# BatteryBoard.net
KiCad netlist of a schematic drawn in EAGLE
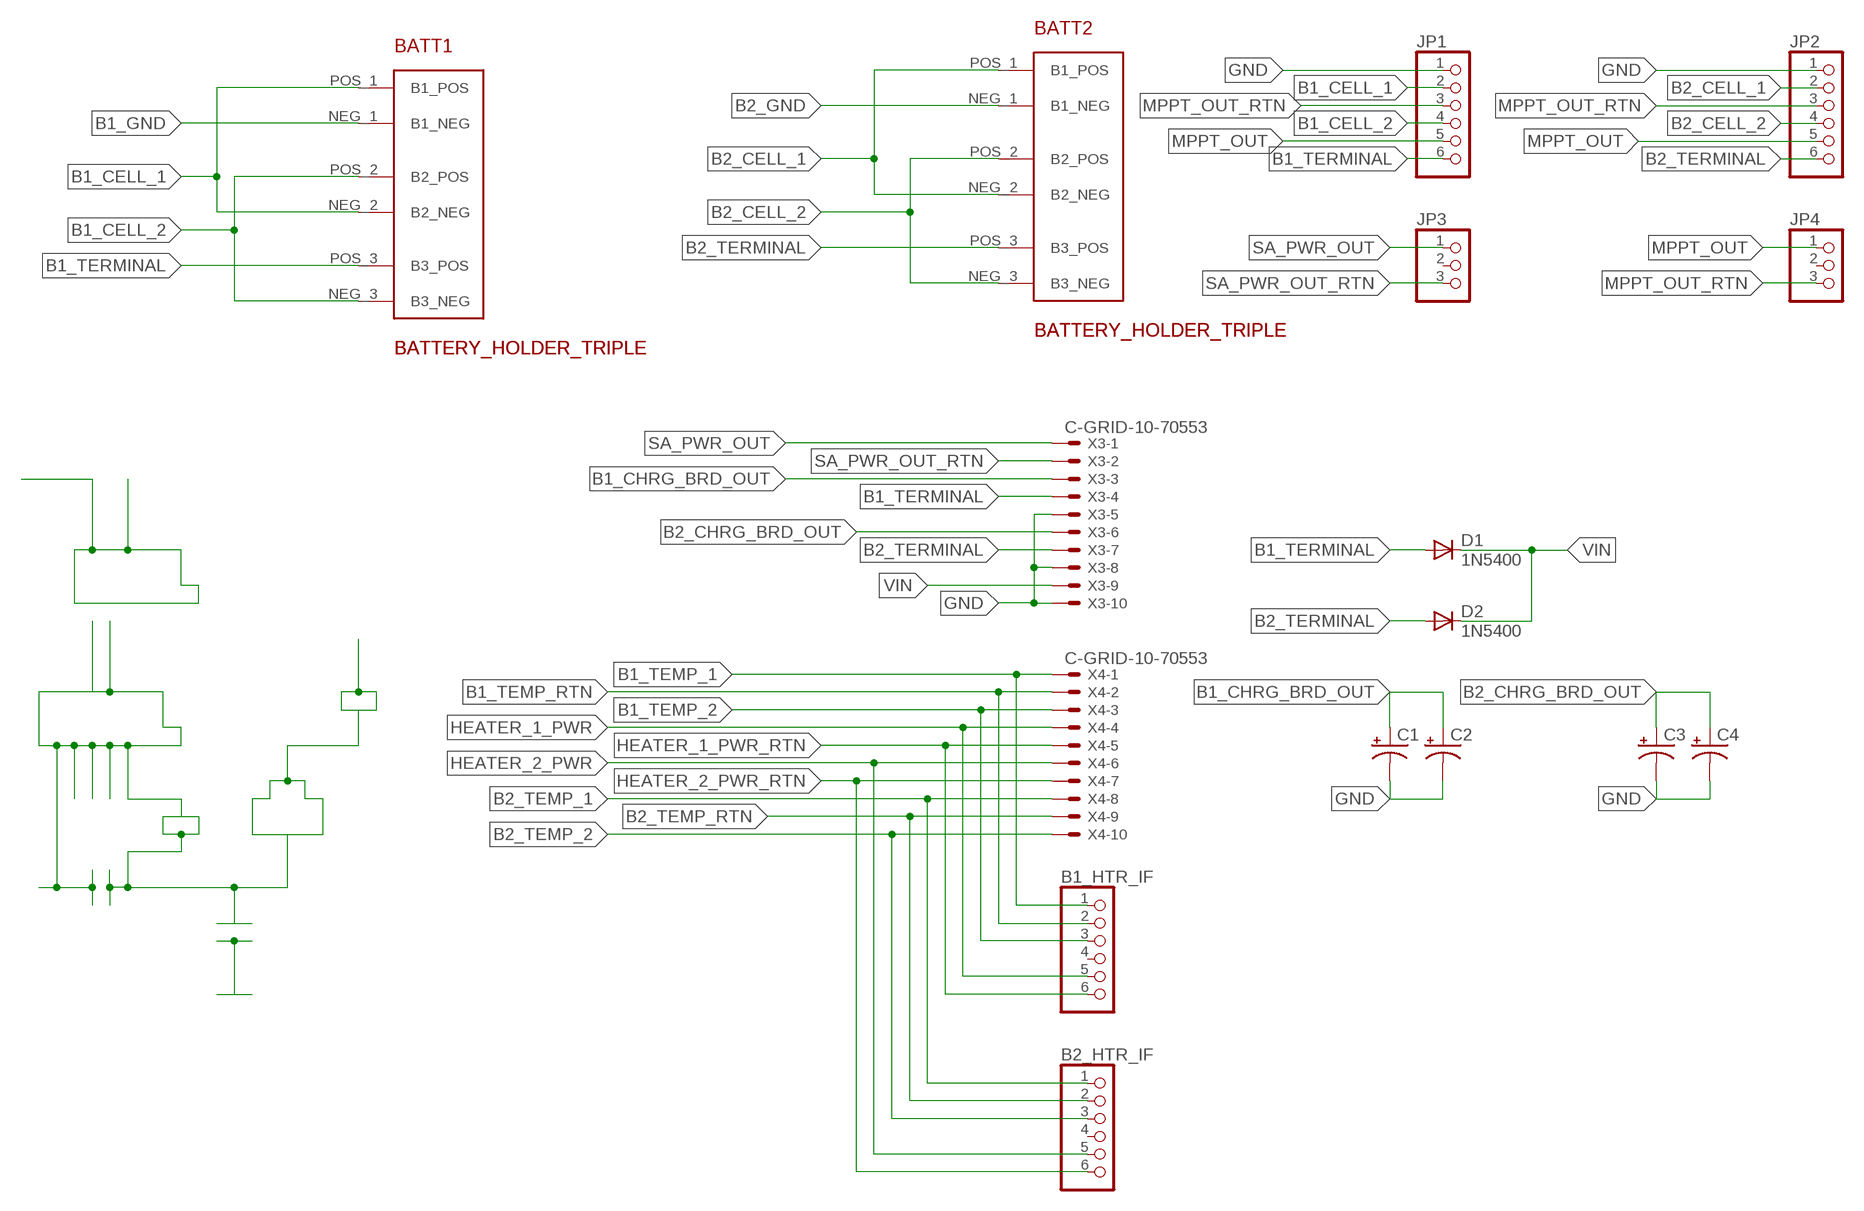
[diagram p0: schematic, sheet 1]

(export (version "E")
  (design (tool "Eeschema 10.0.6"))
  (components
    (comp (ref "B1_HTR_IF")
      (value "PINHD-1X6CLEAN")
      (footprint "eagle-import:1X06-CLEAN")
      (libsource (lib "eagle-import") (part "PINHD-1X6CLEAN"))
    )
    (comp (ref "B2_HTR_IF")
      (value "PINHD-1X6CLEAN")
      (footprint "eagle-import:1X06-CLEAN")
      (libsource (lib "eagle-import") (part "PINHD-1X6CLEAN"))
    )
    (comp (ref "BATT1")
      (value "BATTERY_HOLDER_TRIPLE")
      (footprint "eagle-import:BATT_HOLDER_SINGLE")
      (libsource (lib "eagle-import") (part "BATTERY_HOLDER_TRIPLE"))
    )
    (comp (ref "BATT2")
      (value "BATTERY_HOLDER_TRIPLE")
      (footprint "eagle-import:BATT_HOLDER_SINGLE")
      (libsource (lib "eagle-import") (part "BATTERY_HOLDER_TRIPLE"))
    )
    (comp (ref "C1")
      (value "CPOL-USCT7343")
      (footprint "eagle-import:CT7343")
      (libsource (lib "eagle-import") (part "CPOL-USCT7343"))
    )
    (comp (ref "C2")
      (value "CPOL-USCT7343")
      (footprint "eagle-import:CT7343")
      (libsource (lib "eagle-import") (part "CPOL-USCT7343"))
    )
    (comp (ref "C3")
      (value "CPOL-USCT7343")
      (footprint "eagle-import:CT7343")
      (libsource (lib "eagle-import") (part "CPOL-USCT7343"))
    )
    (comp (ref "C4")
      (value "CPOL-USCT7343")
      (footprint "eagle-import:CT7343")
      (libsource (lib "eagle-import") (part "CPOL-USCT7343"))
    )
    (comp (ref "D1")
      (value "1N5400")
      (footprint "eagle-import:DO201-15")
      (libsource (lib "eagle-import") (part "1N5400"))
    )
    (comp (ref "D2")
      (value "1N5400")
      (footprint "eagle-import:DO201-15")
      (libsource (lib "eagle-import") (part "1N5400"))
    )
    (comp (ref "JP1")
      (value "PINHD-1X6CLEAN")
      (footprint "eagle-import:1X06-CLEAN")
      (libsource (lib "eagle-import") (part "PINHD-1X6CLEAN"))
    )
    (comp (ref "JP2")
      (value "PINHD-1X6CLEAN")
      (footprint "eagle-import:1X06-CLEAN")
      (libsource (lib "eagle-import") (part "PINHD-1X6CLEAN"))
    )
    (comp (ref "JP3")
      (value "PINHD-1X3")
      (footprint "eagle-import:1X03")
      (libsource (lib "eagle-import") (part "PINHD-1X3"))
    )
    (comp (ref "JP4")
      (value "PINHD-1X3")
      (footprint "eagle-import:1X03")
      (libsource (lib "eagle-import") (part "PINHD-1X3"))
    )
    (comp (ref "X3")
      (value "C-GRID-10-70553")
      (footprint "eagle-import:70553-10")
      (libsource (lib "eagle-import") (part "C-GRID-10-70553"))
    )
    (comp (ref "X4")
      (value "C-GRID-10-70553")
      (footprint "eagle-import:70553-10")
      (libsource (lib "eagle-import") (part "C-GRID-10-70553"))
    )
  )
  (nets
    (net (code "1") (name "B1_CELL_1") (class "Default")
      (node (ref "BATT1") (pin "NEG_2") (pinfunction "B2_NEG_NEG_2") (pintype "bidirectional"))
      (node (ref "BATT1") (pin "POS_1") (pinfunction "B1_POS_POS_1") (pintype "bidirectional"))
      (node (ref "JP1") (pin "2") (pinfunction "2_2") (pintype "passive"))
    )
    (net (code "2") (name "B1_CELL_2") (class "Default")
      (node (ref "BATT1") (pin "NEG_3") (pinfunction "B3_NEG_NEG_3") (pintype "bidirectional"))
      (node (ref "BATT1") (pin "POS_2") (pinfunction "B2_POS_POS_2") (pintype "bidirectional"))
      (node (ref "JP1") (pin "4") (pinfunction "4_4") (pintype "passive"))
    )
    (net (code "3") (name "B1_CHRG_BRD_OUT") (class "Default")
      (node (ref "C1") (pin "+") (pinfunction "+_+") (pintype "passive"))
      (node (ref "C2") (pin "+") (pinfunction "+_+") (pintype "passive"))
      (node (ref "X3") (pin "3") (pinfunction "S_3") (pintype "passive"))
    )
    (net (code "4") (name "B1_GND") (class "Default")
      (node (ref "BATT1") (pin "NEG_1") (pinfunction "B1_NEG_NEG_1") (pintype "bidirectional"))
    )
    (net (code "5") (name "B1_TEMP_1") (class "Default")
      (node (ref "B1_HTR_IF") (pin "1") (pinfunction "1_1") (pintype "passive"))
      (node (ref "X4") (pin "1") (pinfunction "S_1") (pintype "passive"))
    )
    (net (code "6") (name "B1_TEMP_2") (class "Default")
      (node (ref "B1_HTR_IF") (pin "3") (pinfunction "3_3") (pintype "passive"))
      (node (ref "X4") (pin "3") (pinfunction "S_3") (pintype "passive"))
    )
    (net (code "7") (name "B1_TEMP_RTN") (class "Default")
      (node (ref "B1_HTR_IF") (pin "2") (pinfunction "2_2") (pintype "passive"))
      (node (ref "X4") (pin "2") (pinfunction "S_2") (pintype "passive"))
    )
    (net (code "8") (name "B1_TERMINAL") (class "Default")
      (node (ref "BATT1") (pin "POS_3") (pinfunction "B3_POS_POS_3") (pintype "bidirectional"))
      (node (ref "D1") (pin "A") (pinfunction "A_A") (pintype "passive"))
      (node (ref "JP1") (pin "6") (pinfunction "6_6") (pintype "passive"))
      (node (ref "X3") (pin "4") (pinfunction "S_4") (pintype "passive"))
    )
    (net (code "9") (name "B2_CELL_1") (class "Default")
      (node (ref "BATT2") (pin "NEG_2") (pinfunction "B2_NEG_NEG_2") (pintype "bidirectional"))
      (node (ref "BATT2") (pin "POS_1") (pinfunction "B1_POS_POS_1") (pintype "bidirectional"))
      (node (ref "JP2") (pin "2") (pinfunction "2_2") (pintype "passive"))
    )
    (net (code "10") (name "B2_CELL_2") (class "Default")
      (node (ref "BATT2") (pin "NEG_3") (pinfunction "B3_NEG_NEG_3") (pintype "bidirectional"))
      (node (ref "BATT2") (pin "POS_2") (pinfunction "B2_POS_POS_2") (pintype "bidirectional"))
      (node (ref "JP2") (pin "4") (pinfunction "4_4") (pintype "passive"))
    )
    (net (code "11") (name "B2_CHRG_BRD_OUT") (class "Default")
      (node (ref "C3") (pin "+") (pinfunction "+_+") (pintype "passive"))
      (node (ref "C4") (pin "+") (pinfunction "+_+") (pintype "passive"))
      (node (ref "X3") (pin "6") (pinfunction "S_6") (pintype "passive"))
    )
    (net (code "12") (name "B2_GND") (class "Default")
      (node (ref "BATT2") (pin "NEG_1") (pinfunction "B1_NEG_NEG_1") (pintype "bidirectional"))
    )
    (net (code "13") (name "B2_TEMP_1") (class "Default")
      (node (ref "B2_HTR_IF") (pin "1") (pinfunction "1_1") (pintype "passive"))
      (node (ref "X4") (pin "8") (pinfunction "S_8") (pintype "passive"))
    )
    (net (code "14") (name "B2_TEMP_2") (class "Default")
      (node (ref "B2_HTR_IF") (pin "3") (pinfunction "3_3") (pintype "passive"))
      (node (ref "X4") (pin "10") (pinfunction "S_10") (pintype "passive"))
    )
    (net (code "15") (name "B2_TEMP_RTN") (class "Default")
      (node (ref "B2_HTR_IF") (pin "2") (pinfunction "2_2") (pintype "passive"))
      (node (ref "X4") (pin "9") (pinfunction "S_9") (pintype "passive"))
    )
    (net (code "16") (name "B2_TERMINAL") (class "Default")
      (node (ref "BATT2") (pin "POS_3") (pinfunction "B3_POS_POS_3") (pintype "bidirectional"))
      (node (ref "D2") (pin "A") (pinfunction "A_A") (pintype "passive"))
      (node (ref "JP2") (pin "6") (pinfunction "6_6") (pintype "passive"))
      (node (ref "X3") (pin "7") (pinfunction "S_7") (pintype "passive"))
    )
    (net (code "17") (name "GND") (class "Default")
      (node (ref "C1") (pin "-") (pinfunction "-_-") (pintype "passive"))
      (node (ref "C2") (pin "-") (pinfunction "-_-") (pintype "passive"))
      (node (ref "C3") (pin "-") (pinfunction "-_-") (pintype "passive"))
      (node (ref "C4") (pin "-") (pinfunction "-_-") (pintype "passive"))
      (node (ref "JP1") (pin "1") (pinfunction "1_1") (pintype "passive"))
      (node (ref "JP2") (pin "1") (pinfunction "1_1") (pintype "passive"))
      (node (ref "X3") (pin "10") (pinfunction "S_10") (pintype "passive"))
      (node (ref "X3") (pin "5") (pinfunction "S_5") (pintype "passive"))
      (node (ref "X3") (pin "8") (pinfunction "S_8") (pintype "passive"))
    )
    (net (code "18") (name "HEATER_1_PWR") (class "Default")
      (node (ref "B1_HTR_IF") (pin "5") (pinfunction "5_5") (pintype "passive"))
      (node (ref "X4") (pin "4") (pinfunction "S_4") (pintype "passive"))
    )
    (net (code "19") (name "HEATER_1_PWR_RTN") (class "Default")
      (node (ref "B1_HTR_IF") (pin "6") (pinfunction "6_6") (pintype "passive"))
      (node (ref "X4") (pin "5") (pinfunction "S_5") (pintype "passive"))
    )
    (net (code "20") (name "HEATER_2_PWR") (class "Default")
      (node (ref "B2_HTR_IF") (pin "5") (pinfunction "5_5") (pintype "passive"))
      (node (ref "X4") (pin "6") (pinfunction "S_6") (pintype "passive"))
    )
    (net (code "21") (name "HEATER_2_PWR_RTN") (class "Default")
      (node (ref "B2_HTR_IF") (pin "6") (pinfunction "6_6") (pintype "passive"))
      (node (ref "X4") (pin "7") (pinfunction "S_7") (pintype "passive"))
    )
    (net (code "22") (name "MPPT_OUT") (class "Default")
      (node (ref "JP1") (pin "5") (pinfunction "5_5") (pintype "passive"))
      (node (ref "JP2") (pin "5") (pinfunction "5_5") (pintype "passive"))
      (node (ref "JP4") (pin "1") (pinfunction "1_1") (pintype "passive"))
    )
    (net (code "23") (name "MPPT_OUT_RTN") (class "Default")
      (node (ref "JP1") (pin "3") (pinfunction "3_3") (pintype "passive"))
      (node (ref "JP2") (pin "3") (pinfunction "3_3") (pintype "passive"))
      (node (ref "JP4") (pin "3") (pinfunction "3_3") (pintype "passive"))
    )
    (net (code "24") (name "SA_PWR_OUT") (class "Default")
      (node (ref "JP3") (pin "1") (pinfunction "1_1") (pintype "passive"))
      (node (ref "X3") (pin "1") (pinfunction "S_1") (pintype "passive"))
    )
    (net (code "25") (name "SA_PWR_OUT_RTN") (class "Default")
      (node (ref "JP3") (pin "3") (pinfunction "3_3") (pintype "passive"))
      (node (ref "X3") (pin "2") (pinfunction "S_2") (pintype "passive"))
    )
    (net (code "26") (name "VIN") (class "Default")
      (node (ref "D1") (pin "C") (pinfunction "C_C") (pintype "passive"))
      (node (ref "D2") (pin "C") (pinfunction "C_C") (pintype "passive"))
      (node (ref "X3") (pin "9") (pinfunction "S_9") (pintype "passive"))
    )
    (net (code "27") (name "unconnected-(B1_HTR_IF-Pad4)") (class "Default")
      (node (ref "B1_HTR_IF") (pin "4") (pinfunction "4_4") (pintype "passive"))
    )
    (net (code "28") (name "unconnected-(B2_HTR_IF-Pad4)") (class "Default")
      (node (ref "B2_HTR_IF") (pin "4") (pinfunction "4_4") (pintype "passive"))
    )
    (net (code "29") (name "unconnected-(JP3-Pad2)") (class "Default")
      (node (ref "JP3") (pin "2") (pinfunction "2_2") (pintype "passive"))
    )
    (net (code "30") (name "unconnected-(JP4-Pad2)") (class "Default")
      (node (ref "JP4") (pin "2") (pinfunction "2_2") (pintype "passive"))
    )
  )
)
